# TCCM.net
KiCad netlist of a schematic drawn in EAGLE
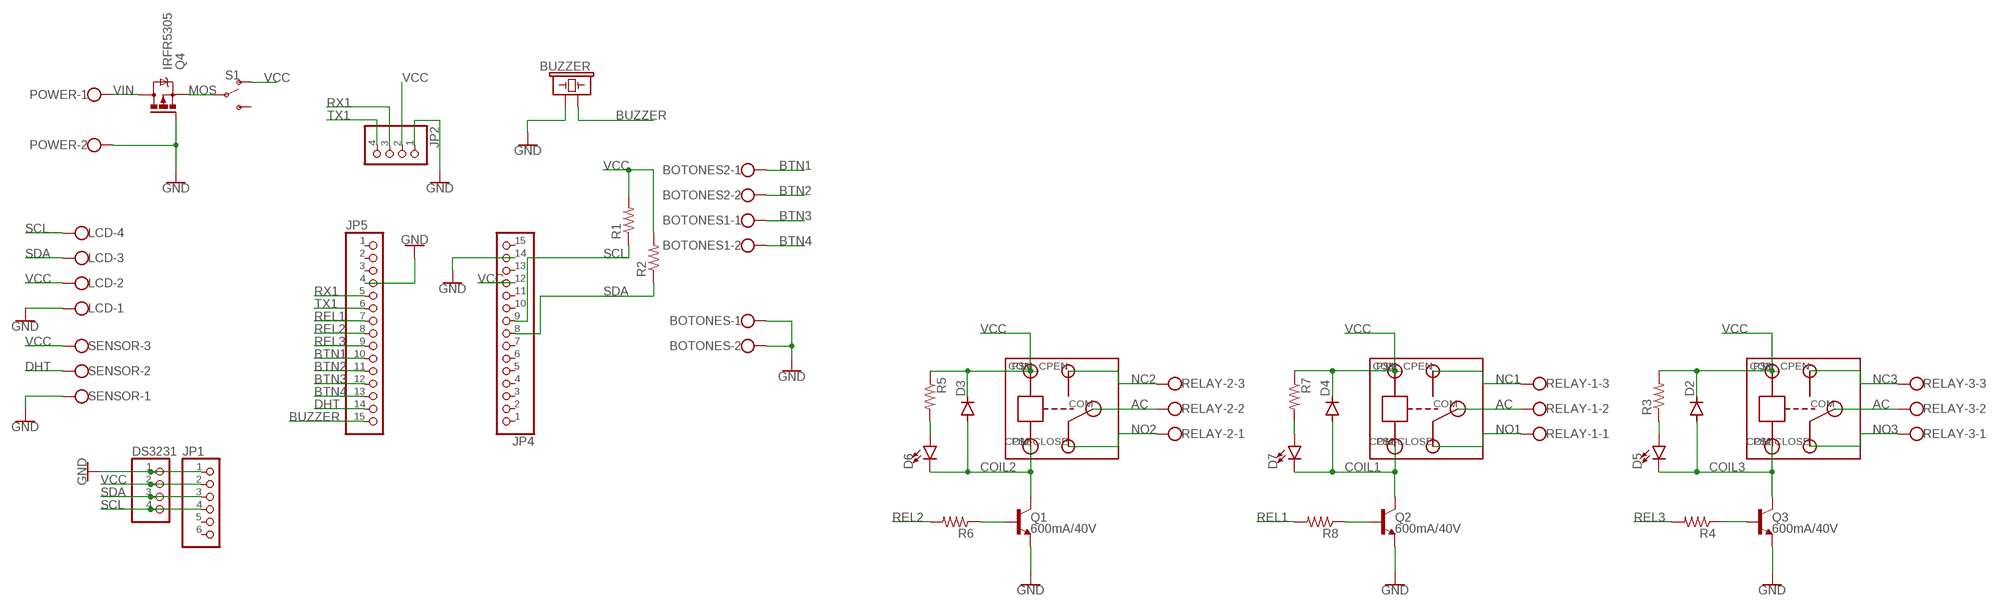
[diagram p0: schematic, sheet 1]

(export (version "E")
  (design (tool "Eeschema 10.0.6"))
  (components
    (comp (ref "BOTONES")
      (value "W237-102")
      (footprint "eagle-import:W237-102")
      (fields (field (name "MPN") "237-102"))
      (libsource (lib "eagle-import") (part "W237-102"))
    )
    (comp (ref "BOTONES1")
      (value "W237-102")
      (footprint "eagle-import:W237-102")
      (fields (field (name "MPN") "237-102"))
      (libsource (lib "eagle-import") (part "W237-102"))
    )
    (comp (ref "BOTONES2")
      (value "W237-102")
      (footprint "eagle-import:W237-102")
      (fields (field (name "MPN") "237-102"))
      (libsource (lib "eagle-import") (part "W237-102"))
    )
    (comp (ref "BUZZER")
      (value "BUZZER-PTH")
      (footprint "eagle-import:BUZZER-12MM")
      (libsource (lib "eagle-import") (part "BUZZER-PTH"))
    )
    (comp (ref "D2")
      (value "1N4148DO35-7")
      (footprint "eagle-import:DO35-7")
      (libsource (lib "eagle-import") (part "1N4148DO35-7"))
    )
    (comp (ref "D3")
      (value "1N4148DO35-7")
      (footprint "eagle-import:DO35-7")
      (libsource (lib "eagle-import") (part "1N4148DO35-7"))
    )
    (comp (ref "D4")
      (value "1N4148DO35-7")
      (footprint "eagle-import:DO35-7")
      (libsource (lib "eagle-import") (part "1N4148DO35-7"))
    )
    (comp (ref "D5")
      (value "LED3MM")
      (footprint "eagle-import:LED_3MM")
      (libsource (lib "eagle-import") (part "LED3MM"))
    )
    (comp (ref "D6")
      (value "LED3MM")
      (footprint "eagle-import:LED_3MM")
      (libsource (lib "eagle-import") (part "LED3MM"))
    )
    (comp (ref "D7")
      (value "LED3MM")
      (footprint "eagle-import:LED_3MM")
      (libsource (lib "eagle-import") (part "LED3MM"))
    )
    (comp (ref "DS3231")
      (value "PINHD-1X4")
      (footprint "eagle-import:1X04")
      (libsource (lib "eagle-import") (part "PINHD-1X4"))
    )
    (comp (ref "JP1")
      (value "PINHD-1X6")
      (footprint "eagle-import:1X06")
      (libsource (lib "eagle-import") (part "PINHD-1X6"))
    )
    (comp (ref "JP2")
      (value "PINHD-1X4")
      (footprint "eagle-import:1X04")
      (libsource (lib "eagle-import") (part "PINHD-1X4"))
    )
    (comp (ref "JP4")
      (value "PINHD-1X15")
      (footprint "eagle-import:1X15")
      (libsource (lib "eagle-import") (part "PINHD-1X15"))
    )
    (comp (ref "JP5")
      (value "PINHD-1X15")
      (footprint "eagle-import:1X15")
      (libsource (lib "eagle-import") (part "PINHD-1X15"))
    )
    (comp (ref "LCD")
      (value "W237-4")
      (footprint "eagle-import:W237-4")
      (libsource (lib "eagle-import") (part "W237-4"))
    )
    (comp (ref "POWER")
      (value "W237-102")
      (footprint "eagle-import:W237-102")
      (fields (field (name "MPN") "237-102"))
      (libsource (lib "eagle-import") (part "W237-102"))
    )
    (comp (ref "Q1")
      (value "600mA/40V")
      (footprint "eagle-import:TO-92")
      (libsource (lib "eagle-import") (part "TRANS_NPN-P2N2222A"))
    )
    (comp (ref "Q2")
      (value "600mA/40V")
      (footprint "eagle-import:TO-92")
      (libsource (lib "eagle-import") (part "TRANS_NPN-P2N2222A"))
    )
    (comp (ref "Q3")
      (value "600mA/40V")
      (footprint "eagle-import:TO-92")
      (libsource (lib "eagle-import") (part "TRANS_NPN-P2N2222A"))
    )
    (comp (ref "Q4")
      (value "IRFR5305")
      (footprint "eagle-import:D-PAK_TO252AA")
      (libsource (lib "eagle-import") (part "IRF?5305R"))
    )
    (comp (ref "R1")
      (value "R-US_0207/7")
      (footprint "eagle-import:0207_7")
      (libsource (lib "eagle-import") (part "R-US_0207/7"))
    )
    (comp (ref "R2")
      (value "R-US_0207/7")
      (footprint "eagle-import:0207_7")
      (libsource (lib "eagle-import") (part "R-US_0207/7"))
    )
    (comp (ref "R3")
      (value "R-US_0207/7")
      (footprint "eagle-import:0207_7")
      (libsource (lib "eagle-import") (part "R-US_0207/7"))
    )
    (comp (ref "R4")
      (value "R-US_0207/7")
      (footprint "eagle-import:0207_7")
      (libsource (lib "eagle-import") (part "R-US_0207/7"))
    )
    (comp (ref "R5")
      (value "R-US_0207/7")
      (footprint "eagle-import:0207_7")
      (libsource (lib "eagle-import") (part "R-US_0207/7"))
    )
    (comp (ref "R6")
      (value "R-US_0207/7")
      (footprint "eagle-import:0207_7")
      (libsource (lib "eagle-import") (part "R-US_0207/7"))
    )
    (comp (ref "R7")
      (value "R-US_0207/7")
      (footprint "eagle-import:0207_7")
      (libsource (lib "eagle-import") (part "R-US_0207/7"))
    )
    (comp (ref "R8")
      (value "R-US_0207/7")
      (footprint "eagle-import:0207_7")
      (libsource (lib "eagle-import") (part "R-US_0207/7"))
    )
    (comp (ref "RELAY-1")
      (value "W237-103")
      (footprint "eagle-import:W237-103")
      (fields (field (name "MPN") "237-103"))
      (libsource (lib "eagle-import") (part "W237-103"))
    )
    (comp (ref "RELAY-2")
      (value "W237-103")
      (footprint "eagle-import:W237-103")
      (fields (field (name "MPN") "237-103"))
      (libsource (lib "eagle-import") (part "W237-103"))
    )
    (comp (ref "RELAY-3")
      (value "W237-103")
      (footprint "eagle-import:W237-103")
      (fields (field (name "MPN") "237-103"))
      (libsource (lib "eagle-import") (part "W237-103"))
    )
    (comp (ref "S1")
      (value "SWITCH-SPDT-PTH-11.6X4.0MM")
      (footprint "eagle-import:SWITCH_SPDT_PTH_11.6X4.0MM")
      (libsource (lib "eagle-import") (part "SWITCH-SPDT-PTH-11.6X4.0MM"))
    )
    (comp (ref "SENSOR")
      (value "W237-103")
      (footprint "eagle-import:W237-103")
      (fields (field (name "MPN") "237-103"))
      (libsource (lib "eagle-import") (part "W237-103"))
    )
    (comp (ref "U$1")
      (value "RELAY")
      (footprint "eagle-import:RELAY")
      (libsource (lib "eagle-import") (part "RELAY"))
    )
    (comp (ref "U$2")
      (value "RELAY")
      (footprint "eagle-import:RELAY")
      (libsource (lib "eagle-import") (part "RELAY"))
    )
    (comp (ref "U$3")
      (value "RELAY")
      (footprint "eagle-import:RELAY")
      (libsource (lib "eagle-import") (part "RELAY"))
    )
  )
  (nets
    (net (code "1") (name "/AC") (class "Default")
      (node (ref "RELAY-1") (pin "2") (pinfunction "KL_2") (pintype "passive"))
      (node (ref "RELAY-2") (pin "2") (pinfunction "KL_2") (pintype "passive"))
      (node (ref "RELAY-3") (pin "2") (pinfunction "KL_2") (pintype "passive"))
      (node (ref "U$1") (pin "COM") (pinfunction "COM_COM") (pintype "bidirectional"))
      (node (ref "U$2") (pin "COM") (pinfunction "COM_COM") (pintype "bidirectional"))
      (node (ref "U$3") (pin "COM") (pinfunction "COM_COM") (pintype "bidirectional"))
    )
    (net (code "2") (name "/BTN1") (class "Default")
      (node (ref "BOTONES2") (pin "1") (pinfunction "KL_1") (pintype "passive"))
      (node (ref "JP5") (pin "10") (pinfunction "10_10") (pintype "passive"))
    )
    (net (code "3") (name "/BTN2") (class "Default")
      (node (ref "BOTONES2") (pin "2") (pinfunction "KL_2") (pintype "passive"))
      (node (ref "JP5") (pin "11") (pinfunction "11_11") (pintype "passive"))
    )
    (net (code "4") (name "/BTN3") (class "Default")
      (node (ref "BOTONES1") (pin "1") (pinfunction "KL_1") (pintype "passive"))
      (node (ref "JP5") (pin "12") (pinfunction "12_12") (pintype "passive"))
    )
    (net (code "5") (name "/BTN4") (class "Default")
      (node (ref "BOTONES1") (pin "2") (pinfunction "KL_2") (pintype "passive"))
      (node (ref "JP5") (pin "13") (pinfunction "13_13") (pintype "passive"))
    )
    (net (code "6") (name "/BUZZER") (class "Default")
      (node (ref "BUZZER") (pin "+") (pinfunction "1_+") (pintype "passive"))
      (node (ref "JP5") (pin "15") (pinfunction "15_15") (pintype "passive"))
    )
    (net (code "7") (name "/COIL1") (class "Default")
      (node (ref "D4") (pin "A") (pinfunction "A_A") (pintype "passive"))
      (node (ref "D7") (pin "K") (pinfunction "C_K") (pintype "passive"))
      (node (ref "Q2") (pin "1") (pinfunction "C_1") (pintype "passive"))
      (node (ref "U$2") (pin "P$2") (pinfunction "GND_P$2") (pintype "bidirectional"))
    )
    (net (code "8") (name "/COIL2") (class "Default")
      (node (ref "D3") (pin "A") (pinfunction "A_A") (pintype "passive"))
      (node (ref "D6") (pin "K") (pinfunction "C_K") (pintype "passive"))
      (node (ref "Q1") (pin "1") (pinfunction "C_1") (pintype "passive"))
      (node (ref "U$1") (pin "P$2") (pinfunction "GND_P$2") (pintype "bidirectional"))
    )
    (net (code "9") (name "/COIL3") (class "Default")
      (node (ref "D2") (pin "A") (pinfunction "A_A") (pintype "passive"))
      (node (ref "D5") (pin "K") (pinfunction "C_K") (pintype "passive"))
      (node (ref "Q3") (pin "1") (pinfunction "C_1") (pintype "passive"))
      (node (ref "U$3") (pin "P$2") (pinfunction "GND_P$2") (pintype "bidirectional"))
    )
    (net (code "10") (name "/DHT") (class "Default")
      (node (ref "JP5") (pin "14") (pinfunction "14_14") (pintype "passive"))
      (node (ref "SENSOR") (pin "2") (pinfunction "KL_2") (pintype "passive"))
    )
    (net (code "11") (name "/MOS") (class "Default")
      (node (ref "Q4") (pin "3") (pinfunction "S_3") (pintype "passive"))
      (node (ref "S1") (pin "2") (pinfunction "P_2") (pintype "passive"))
    )
    (net (code "12") (name "/NC1") (class "Default")
      (node (ref "RELAY-1") (pin "3") (pinfunction "KL_3") (pintype "passive"))
      (node (ref "U$2") (pin "COM_CPEN") (pinfunction "COM-OPEN_COM_CPEN") (pintype "bidirectional"))
    )
    (net (code "13") (name "/NC2") (class "Default")
      (node (ref "RELAY-2") (pin "3") (pinfunction "KL_3") (pintype "passive"))
      (node (ref "U$1") (pin "COM_CPEN") (pinfunction "COM-OPEN_COM_CPEN") (pintype "bidirectional"))
    )
    (net (code "14") (name "/NC3") (class "Default")
      (node (ref "RELAY-3") (pin "3") (pinfunction "KL_3") (pintype "passive"))
      (node (ref "U$3") (pin "COM_CPEN") (pinfunction "COM-OPEN_COM_CPEN") (pintype "bidirectional"))
    )
    (net (code "15") (name "/NO1") (class "Default")
      (node (ref "RELAY-1") (pin "1") (pinfunction "KL_1") (pintype "passive"))
      (node (ref "U$2") (pin "COM-CLOSE") (pinfunction "COM-CLOSE_COM-CLOSE") (pintype "bidirectional"))
    )
    (net (code "16") (name "/NO2") (class "Default")
      (node (ref "RELAY-2") (pin "1") (pinfunction "KL_1") (pintype "passive"))
      (node (ref "U$1") (pin "COM-CLOSE") (pinfunction "COM-CLOSE_COM-CLOSE") (pintype "bidirectional"))
    )
    (net (code "17") (name "/NO3") (class "Default")
      (node (ref "RELAY-3") (pin "1") (pinfunction "KL_1") (pintype "passive"))
      (node (ref "U$3") (pin "COM-CLOSE") (pinfunction "COM-CLOSE_COM-CLOSE") (pintype "bidirectional"))
    )
    (net (code "18") (name "/REL1") (class "Default")
      (node (ref "JP5") (pin "7") (pinfunction "7_7") (pintype "passive"))
      (node (ref "R8") (pin "2") (pinfunction "2_2") (pintype "passive"))
    )
    (net (code "19") (name "/REL2") (class "Default")
      (node (ref "JP5") (pin "8") (pinfunction "8_8") (pintype "passive"))
      (node (ref "R6") (pin "2") (pinfunction "2_2") (pintype "passive"))
    )
    (net (code "20") (name "/REL3") (class "Default")
      (node (ref "JP5") (pin "9") (pinfunction "9_9") (pintype "passive"))
      (node (ref "R4") (pin "2") (pinfunction "2_2") (pintype "passive"))
    )
    (net (code "21") (name "/RX1") (class "Default")
      (node (ref "JP2") (pin "3") (pinfunction "3_3") (pintype "passive"))
      (node (ref "JP5") (pin "5") (pinfunction "5_5") (pintype "passive"))
    )
    (net (code "22") (name "/SCL") (class "Default")
      (node (ref "DS3231") (pin "4") (pinfunction "4_4") (pintype "passive"))
      (node (ref "JP1") (pin "4") (pinfunction "4_4") (pintype "passive"))
      (node (ref "JP4") (pin "9") (pinfunction "9_9") (pintype "passive"))
      (node (ref "LCD") (pin "4") (pinfunction "KL_4") (pintype "passive"))
      (node (ref "R1") (pin "1") (pinfunction "1_1") (pintype "passive"))
    )
    (net (code "23") (name "/SDA") (class "Default")
      (node (ref "DS3231") (pin "3") (pinfunction "3_3") (pintype "passive"))
      (node (ref "JP1") (pin "3") (pinfunction "3_3") (pintype "passive"))
      (node (ref "JP4") (pin "8") (pinfunction "8_8") (pintype "passive"))
      (node (ref "LCD") (pin "3") (pinfunction "KL_3") (pintype "passive"))
      (node (ref "R2") (pin "1") (pinfunction "1_1") (pintype "passive"))
    )
    (net (code "24") (name "/TX1") (class "Default")
      (node (ref "JP2") (pin "4") (pinfunction "4_4") (pintype "passive"))
      (node (ref "JP5") (pin "6") (pinfunction "6_6") (pintype "passive"))
    )
    (net (code "25") (name "/VCC") (class "Default")
      (node (ref "D2") (pin "C") (pinfunction "C_C") (pintype "passive"))
      (node (ref "D3") (pin "C") (pinfunction "C_C") (pintype "passive"))
      (node (ref "D4") (pin "C") (pinfunction "C_C") (pintype "passive"))
      (node (ref "DS3231") (pin "2") (pinfunction "2_2") (pintype "passive"))
      (node (ref "JP1") (pin "2") (pinfunction "2_2") (pintype "passive"))
      (node (ref "JP2") (pin "2") (pinfunction "2_2") (pintype "passive"))
      (node (ref "JP4") (pin "12") (pinfunction "12_12") (pintype "passive"))
      (node (ref "LCD") (pin "2") (pinfunction "KL_2") (pintype "passive"))
      (node (ref "R1") (pin "2") (pinfunction "2_2") (pintype "passive"))
      (node (ref "R2") (pin "2") (pinfunction "2_2") (pintype "passive"))
      (node (ref "R3") (pin "2") (pinfunction "2_2") (pintype "passive"))
      (node (ref "R5") (pin "1") (pinfunction "1_1") (pintype "passive"))
      (node (ref "R7") (pin "1") (pinfunction "1_1") (pintype "passive"))
      (node (ref "S1") (pin "1") (pinfunction "O_1") (pintype "passive"))
      (node (ref "SENSOR") (pin "3") (pinfunction "KL_3") (pintype "passive"))
      (node (ref "U$1") (pin "P$1") (pinfunction "IN_P$1") (pintype "bidirectional"))
      (node (ref "U$2") (pin "P$1") (pinfunction "IN_P$1") (pintype "bidirectional"))
      (node (ref "U$3") (pin "P$1") (pinfunction "IN_P$1") (pintype "bidirectional"))
    )
    (net (code "26") (name "/VIN") (class "Default")
      (node (ref "POWER") (pin "1") (pinfunction "KL_1") (pintype "passive"))
      (node (ref "Q4") (pin "4") (pinfunction "D_4") (pintype "passive"))
    )
    (net (code "27") (name "GND") (class "Default")
      (node (ref "BOTONES") (pin "1") (pinfunction "KL_1") (pintype "passive"))
      (node (ref "BOTONES") (pin "2") (pinfunction "KL_2") (pintype "passive"))
      (node (ref "BUZZER") (pin "-") (pinfunction "2_-") (pintype "passive"))
      (node (ref "DS3231") (pin "1") (pinfunction "1_1") (pintype "passive"))
      (node (ref "JP1") (pin "1") (pinfunction "1_1") (pintype "passive"))
      (node (ref "JP2") (pin "1") (pinfunction "1_1") (pintype "passive"))
      (node (ref "JP4") (pin "14") (pinfunction "14_14") (pintype "passive"))
      (node (ref "JP5") (pin "4") (pinfunction "4_4") (pintype "passive"))
      (node (ref "LCD") (pin "1") (pinfunction "KL_1") (pintype "passive"))
      (node (ref "POWER") (pin "2") (pinfunction "KL_2") (pintype "passive"))
      (node (ref "Q1") (pin "3") (pinfunction "E_3") (pintype "passive"))
      (node (ref "Q2") (pin "3") (pinfunction "E_3") (pintype "passive"))
      (node (ref "Q3") (pin "3") (pinfunction "E_3") (pintype "passive"))
      (node (ref "Q4") (pin "1") (pinfunction "G_1") (pintype "passive"))
      (node (ref "SENSOR") (pin "1") (pinfunction "KL_1") (pintype "passive"))
    )
    (net (code "28") (name "Net-(D5-PadA)") (class "Default")
      (node (ref "D5") (pin "A") (pinfunction "A_A") (pintype "passive"))
      (node (ref "R3") (pin "1") (pinfunction "1_1") (pintype "passive"))
    )
    (net (code "29") (name "Net-(D6-PadA)") (class "Default")
      (node (ref "D6") (pin "A") (pinfunction "A_A") (pintype "passive"))
      (node (ref "R5") (pin "2") (pinfunction "2_2") (pintype "passive"))
    )
    (net (code "30") (name "Net-(D7-PadA)") (class "Default")
      (node (ref "D7") (pin "A") (pinfunction "A_A") (pintype "passive"))
      (node (ref "R7") (pin "2") (pinfunction "2_2") (pintype "passive"))
    )
    (net (code "31") (name "Net-(Q1-B)") (class "Default")
      (node (ref "Q1") (pin "2") (pinfunction "B_2") (pintype "passive"))
      (node (ref "R6") (pin "1") (pinfunction "1_1") (pintype "passive"))
    )
    (net (code "32") (name "Net-(Q2-B)") (class "Default")
      (node (ref "Q2") (pin "2") (pinfunction "B_2") (pintype "passive"))
      (node (ref "R8") (pin "1") (pinfunction "1_1") (pintype "passive"))
    )
    (net (code "33") (name "Net-(Q3-B)") (class "Default")
      (node (ref "Q3") (pin "2") (pinfunction "B_2") (pintype "passive"))
      (node (ref "R4") (pin "1") (pinfunction "1_1") (pintype "passive"))
    )
    (net (code "34") (name "unconnected-(JP1-Pad5)") (class "Default")
      (node (ref "JP1") (pin "5") (pinfunction "5_5") (pintype "passive"))
    )
    (net (code "35") (name "unconnected-(JP1-Pad6)") (class "Default")
      (node (ref "JP1") (pin "6") (pinfunction "6_6") (pintype "passive"))
    )
    (net (code "36") (name "unconnected-(JP4-Pad1)") (class "Default")
      (node (ref "JP4") (pin "1") (pinfunction "1_1") (pintype "passive"))
    )
    (net (code "37") (name "unconnected-(JP4-Pad2)") (class "Default")
      (node (ref "JP4") (pin "2") (pinfunction "2_2") (pintype "passive"))
    )
    (net (code "38") (name "unconnected-(JP4-Pad3)") (class "Default")
      (node (ref "JP4") (pin "3") (pinfunction "3_3") (pintype "passive"))
    )
    (net (code "39") (name "unconnected-(JP4-Pad4)") (class "Default")
      (node (ref "JP4") (pin "4") (pinfunction "4_4") (pintype "passive"))
    )
    (net (code "40") (name "unconnected-(JP4-Pad5)") (class "Default")
      (node (ref "JP4") (pin "5") (pinfunction "5_5") (pintype "passive"))
    )
    (net (code "41") (name "unconnected-(JP4-Pad6)") (class "Default")
      (node (ref "JP4") (pin "6") (pinfunction "6_6") (pintype "passive"))
    )
    (net (code "42") (name "unconnected-(JP4-Pad7)") (class "Default")
      (node (ref "JP4") (pin "7") (pinfunction "7_7") (pintype "passive"))
    )
    (net (code "43") (name "unconnected-(JP4-Pad10)") (class "Default")
      (node (ref "JP4") (pin "10") (pinfunction "10_10") (pintype "passive"))
    )
    (net (code "44") (name "unconnected-(JP4-Pad11)") (class "Default")
      (node (ref "JP4") (pin "11") (pinfunction "11_11") (pintype "passive"))
    )
    (net (code "45") (name "unconnected-(JP4-Pad13)") (class "Default")
      (node (ref "JP4") (pin "13") (pinfunction "13_13") (pintype "passive"))
    )
    (net (code "46") (name "unconnected-(JP4-Pad15)") (class "Default")
      (node (ref "JP4") (pin "15") (pinfunction "15_15") (pintype "passive"))
    )
    (net (code "47") (name "unconnected-(JP5-Pad1)") (class "Default")
      (node (ref "JP5") (pin "1") (pinfunction "1_1") (pintype "passive"))
    )
    (net (code "48") (name "unconnected-(JP5-Pad2)") (class "Default")
      (node (ref "JP5") (pin "2") (pinfunction "2_2") (pintype "passive"))
    )
    (net (code "49") (name "unconnected-(JP5-Pad3)") (class "Default")
      (node (ref "JP5") (pin "3") (pinfunction "3_3") (pintype "passive"))
    )
    (net (code "50") (name "unconnected-(S1-S-Pad3)") (class "Default")
      (node (ref "S1") (pin "3") (pinfunction "S_3") (pintype "passive"))
    )
  )
)
